# sd_flash_eeprom.net
KiCad netlist of a schematic drawn in Altium Designer
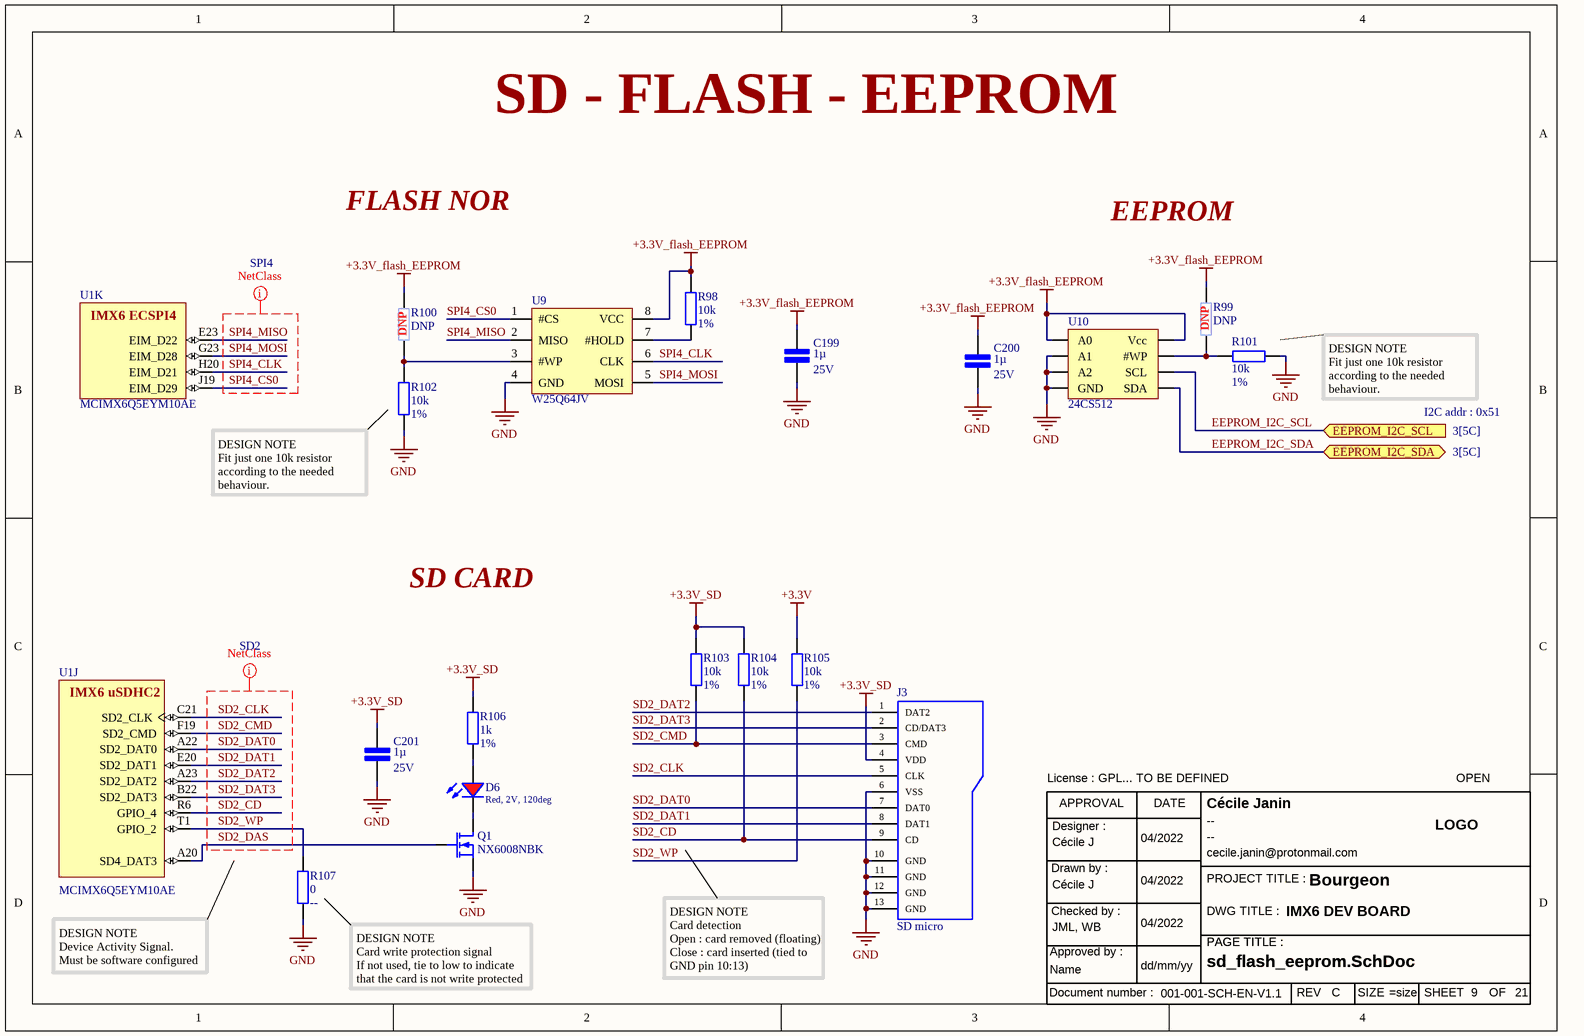
[diagram p0: sd_flash_eeprom.SchDoc]

(export (version "E")
  (design (tool "Eeschema 10.0.6"))
  (components
    (comp (ref "C199")
      (value "1µ")
      (footprint "Cap cer 0402/1005")
      (description "cap cer 1µ 25V 10% X5R 0402")
      (fields (field (name "TENSION DU DIÉLECTRIQUE") "25V"))
      (libsource (lib "First Board IMX6") (part "cap 1µ 25V"))
    )
    (comp (ref "C200")
      (value "1µ")
      (footprint "Cap cer 0402/1005")
      (description "cap cer 1µ 25V 10% X5R 0402")
      (fields (field (name "TENSION DU DIÉLECTRIQUE") "25V"))
      (libsource (lib "First Board IMX6") (part "cap 1µ 25V"))
    )
    (comp (ref "C201")
      (value "1µ")
      (footprint "Cap cer 0402/1005")
      (description "cap cer 1µ 25V 10% X5R 0402")
      (fields (field (name "TENSION DU DIÉLECTRIQUE") "25V"))
      (libsource (lib "First Board IMX6") (part "cap 1µ 25V"))
    )
    (comp (ref "D6")
      (value "Red, 2V, 120deg")
      (footprint "LED red 0603")
      (description "WL-SMCC SMD Mono-color Chip LED Compact, size 0603, Red, 2V, 120deg 150060RS73220")
      (fields (field (name "PART NUMBER") "150060RS73220") (field (name "PUBLISHER") "Wurth Elektronik"))
      (libsource (lib "First Board IMX6") (part "LED Red 0603"))
    )
    (comp (ref "J3")
      (value "SD micro")
      (footprint "SD_micro_693071020811")
      (description "SD micro card, push & push")
      (libsource (lib "First Board IMX6") (part "SD_micro_693071020811"))
    )
    (comp (ref "Q1")
      (value "NX6008NBK")
      (footprint "Sot-23-3 mosfet")
      (description "SOT-23-3 270mA 60V ESD protected 2kV HBM")
      (libsource (lib "First Board IMX6") (part "Tr nmos NX6008NBK"))
    )
    (comp (ref "R98")
      (value "10k")
      (footprint "Res 0402/1005")
      (description "res 10k 1% 0402")
      (fields (field (name "POURCENTAGE") "1%"))
      (libsource (lib "First Board IMX6") (part "res 10k 1%"))
    )
    (comp (ref "R99")
      (value "DNP")
      (footprint "Res 0402/1005")
      (description "res DNP 0403")
      (libsource (lib "First Board IMX6") (part "res DNP 0402"))
    )
    (comp (ref "R100")
      (value "DNP")
      (footprint "Res 0402/1005")
      (description "res DNP 0403")
      (libsource (lib "First Board IMX6") (part "res DNP 0402"))
    )
    (comp (ref "R101")
      (value "10k")
      (footprint "Res 0402/1005")
      (description "res 10k 1% 0402")
      (fields (field (name "POURCENTAGE") "1%"))
      (libsource (lib "First Board IMX6") (part "res 10k 1%"))
    )
    (comp (ref "R102")
      (value "10k")
      (footprint "Res 0402/1005")
      (description "res 10k 1% 0402")
      (fields (field (name "POURCENTAGE") "1%"))
      (libsource (lib "First Board IMX6") (part "res 10k 1%"))
    )
    (comp (ref "R103")
      (value "10k")
      (footprint "Res 0402/1005")
      (description "res 10k 1% 0402")
      (fields (field (name "POURCENTAGE") "1%"))
      (libsource (lib "First Board IMX6") (part "res 10k 1%"))
    )
    (comp (ref "R104")
      (value "10k")
      (footprint "Res 0402/1005")
      (description "res 10k 1% 0402")
      (fields (field (name "POURCENTAGE") "1%"))
      (libsource (lib "First Board IMX6") (part "res 10k 1%"))
    )
    (comp (ref "R105")
      (value "10k")
      (footprint "Res 0402/1005")
      (description "res 10k 1% 0402")
      (fields (field (name "POURCENTAGE") "1%"))
      (libsource (lib "First Board IMX6") (part "res 10k 1%"))
    )
    (comp (ref "R106")
      (value "1k")
      (footprint "Res 0402/1005")
      (description "res 1k 1% 0402")
      (fields (field (name "POURCENTAGE") "1%"))
      (libsource (lib "First Board IMX6") (part "res 1k 1%"))
    )
    (comp (ref "R107")
      (value "0")
      (footprint "Res 0603/1603")
      (description "res 0603")
      (fields (field (name "POURCENTAGE") "--"))
      (libsource (lib "First Board IMX6") (part "res 0Ohm"))
    )
    (comp (ref "TB8")
      (value "Title bloc ANSI modified")
      (libsource (lib "First Board IMX6") (part "Title bloc ANSI"))
    )
    (comp (ref "U1")
      (value "MCIMX6Q5EYM10AE")
      (footprint "FRES-2197-01")
      (fields
        (field (name "PARTNUMBER") "MCIMX6Q5EYM10ACR")
        (field (name "MANUFACTURER") "Freescale Semiconductor")
      )
      (libsource (lib "First Board IMX6") (part "IMX6Q5EYM10AE"))
    )
    (comp (ref "U9")
      (value "W25Q64JV")
      (footprint "SOIC 8 pin FLSH (longer)")
      (description "64Mbit flash NOR")
      (libsource (lib "First Board IMX6") (part "IC W25Q64JV"))
    )
    (comp (ref "U10")
      (value "24CS512")
      (footprint "soic-8")
      (description "EEPROM 512kbit")
      (libsource (lib "First Board IMX6") (part "IC 24CS512"))
    )
  )
  (nets
    (net (code "1") (name "+3.3V") (class "Default") (node (ref "R105") (pin "2") (pintype "passive")))
    (net (code "2") (name "+3.3V_SD") (class "Default")
      (node (ref "C201") (pin "1") (pinfunction "3_1") (pintype "passive"))
      (node (ref "J3") (pin "4") (pinfunction "VDD_4") (pintype "passive"))
      (node (ref "R103") (pin "2") (pintype "passive"))
      (node (ref "R104") (pin "2") (pintype "passive"))
      (node (ref "R106") (pin "2") (pintype "passive"))
    )
    (net (code "3") (name "+3.3V_flash_EEPROM") (class "Default")
      (node (ref "C199") (pin "1") (pinfunction "3_1") (pintype "passive"))
      (node (ref "C200") (pin "1") (pinfunction "3_1") (pintype "passive"))
      (node (ref "R100") (pin "2") (pintype "passive"))
      (node (ref "R98") (pin "2") (pintype "passive"))
      (node (ref "R99") (pin "2") (pintype "passive"))
      (node (ref "U10") (pin "1") (pinfunction "A0_1") (pintype "passive"))
      (node (ref "U10") (pin "8") (pinfunction "Vcc_8") (pintype "passive"))
      (node (ref "U9") (pin "8") (pinfunction "VCC_8") (pintype "passive"))
    )
    (net (code "4") (name "/EEPROM_I2C_SCL") (class "Default")
      (node (ref "U10") (pin "6") (pinfunction "SCL_6") (pintype "passive"))
    )
    (net (code "5") (name "/EEPROM_I2C_SDA") (class "Default")
      (node (ref "U10") (pin "5") (pinfunction "SDA_5") (pintype "passive"))
    )
    (net (code "6") (name "/SD2_CD") (class "Default")
      (node (ref "J3") (pin "9") (pinfunction "CD_9") (pintype "passive"))
      (node (ref "R104") (pin "1") (pintype "passive"))
      (node (ref "U1") (pin "R6") (pinfunction "GPIO_4_R6") (pintype "bidirectional"))
    )
    (net (code "7") (name "/SD2_CLK") (class "Default")
      (node (ref "J3") (pin "5") (pinfunction "CLK_5") (pintype "passive"))
      (node (ref "U1") (pin "C21") (pinfunction "SD2_CLK_C21") (pintype "bidirectional"))
    )
    (net (code "8") (name "/SD2_CMD") (class "Default")
      (node (ref "J3") (pin "3") (pinfunction "CMD_3") (pintype "passive"))
      (node (ref "R103") (pin "1") (pintype "passive"))
      (node (ref "U1") (pin "F19") (pinfunction "SD2_CMD_F19") (pintype "bidirectional"))
    )
    (net (code "9") (name "/SD2_DAS") (class "Default")
      (node (ref "Q1") (pin "G") (pinfunction "G_G") (pintype "passive"))
      (node (ref "U1") (pin "A20") (pinfunction "SD4_DAT3_A20") (pintype "bidirectional"))
    )
    (net (code "10") (name "/SD2_DAT0") (class "Default")
      (node (ref "J3") (pin "7") (pinfunction "DAT0_7") (pintype "passive"))
      (node (ref "U1") (pin "A22") (pinfunction "SD2_DAT0_A22") (pintype "bidirectional"))
    )
    (net (code "11") (name "/SD2_DAT1") (class "Default")
      (node (ref "J3") (pin "8") (pinfunction "DAT1_8") (pintype "passive"))
      (node (ref "U1") (pin "E20") (pinfunction "SD2_DAT1_E20") (pintype "bidirectional"))
    )
    (net (code "12") (name "/SD2_DAT2") (class "Default")
      (node (ref "J3") (pin "1") (pinfunction "DAT2_1") (pintype "passive"))
      (node (ref "U1") (pin "A23") (pinfunction "SD2_DAT2_A23") (pintype "bidirectional"))
    )
    (net (code "13") (name "/SD2_DAT3") (class "Default")
      (node (ref "J3") (pin "2") (pinfunction "CD/DAT3_2") (pintype "passive"))
      (node (ref "U1") (pin "B22") (pinfunction "SD2_DAT3_B22") (pintype "bidirectional"))
    )
    (net (code "14") (name "/SD2_WP") (class "Default")
      (node (ref "R105") (pin "1") (pintype "passive"))
      (node (ref "R107") (pin "2") (pintype "passive"))
      (node (ref "U1") (pin "T1") (pinfunction "GPIO_2_T1") (pintype "bidirectional"))
    )
    (net (code "15") (name "/SPI4_CLK") (class "Default")
      (node (ref "U1") (pin "H20") (pinfunction "EIM_D21_H20") (pintype "bidirectional"))
      (node (ref "U9") (pin "6") (pinfunction "CLK_6") (pintype "passive"))
    )
    (net (code "16") (name "/SPI4_CS0") (class "Default")
      (node (ref "U1") (pin "J19") (pinfunction "EIM_D29_J19") (pintype "bidirectional"))
      (node (ref "U9") (pin "1") (pinfunction "#CS_1") (pintype "passive"))
    )
    (net (code "17") (name "/SPI4_MISO") (class "Default")
      (node (ref "U1") (pin "E23") (pinfunction "EIM_D22_E23") (pintype "bidirectional"))
      (node (ref "U9") (pin "2") (pinfunction "MISO_2") (pintype "passive"))
    )
    (net (code "18") (name "/SPI4_MOSI") (class "Default")
      (node (ref "U1") (pin "G23") (pinfunction "EIM_D28_G23") (pintype "bidirectional"))
      (node (ref "U9") (pin "5") (pinfunction "MOSI_5") (pintype "passive"))
    )
    (net (code "19") (name "GND") (class "Default")
      (node (ref "C199") (pin "2") (pinfunction "4_2") (pintype "passive"))
      (node (ref "C200") (pin "2") (pinfunction "4_2") (pintype "passive"))
      (node (ref "C201") (pin "2") (pinfunction "4_2") (pintype "passive"))
      (node (ref "J3") (pin "10") (pinfunction "GND_10") (pintype "passive"))
      (node (ref "J3") (pin "11") (pinfunction "GND_11") (pintype "passive"))
      (node (ref "J3") (pin "12") (pinfunction "GND_12") (pintype "passive"))
      (node (ref "J3") (pin "13") (pinfunction "GND_13") (pintype "passive"))
      (node (ref "J3") (pin "6") (pinfunction "VSS_6") (pintype "passive"))
      (node (ref "Q1") (pin "S") (pinfunction "S_S") (pintype "passive"))
      (node (ref "R101") (pin "1") (pintype "passive"))
      (node (ref "R102") (pin "1") (pintype "passive"))
      (node (ref "R107") (pin "1") (pintype "passive"))
      (node (ref "U10") (pin "2") (pinfunction "A1_2") (pintype "passive"))
      (node (ref "U10") (pin "3") (pinfunction "A2_3") (pintype "passive"))
      (node (ref "U10") (pin "4") (pinfunction "GND_4") (pintype "passive"))
      (node (ref "U9") (pin "4") (pinfunction "GND_4") (pintype "passive"))
    )
    (net (code "20") (name "Net-(D6-A)") (class "Default")
      (node (ref "D6") (pin "2") (pinfunction "A_2") (pintype "passive"))
      (node (ref "R106") (pin "1") (pintype "passive"))
    )
    (net (code "21") (name "Net-(D6-K)") (class "Default")
      (node (ref "D6") (pin "1") (pinfunction "K_1") (pintype "passive"))
      (node (ref "Q1") (pin "D") (pinfunction "D_D") (pintype "passive"))
    )
    (net (code "22") (name "Net-(U9-#HOLD)") (class "Default")
      (node (ref "R98") (pin "1") (pintype "passive"))
      (node (ref "U9") (pin "7") (pinfunction "#HOLD_7") (pintype "passive"))
    )
    (net (code "23") (name "Net-(U9-#WP)") (class "Default")
      (node (ref "R100") (pin "1") (pintype "passive"))
      (node (ref "R102") (pin "2") (pintype "passive"))
      (node (ref "U9") (pin "3") (pinfunction "#WP_3") (pintype "passive"))
    )
    (net (code "24") (name "Net-(U10-#WP)") (class "Default")
      (node (ref "R101") (pin "2") (pintype "passive"))
      (node (ref "R99") (pin "1") (pintype "passive"))
      (node (ref "U10") (pin "7") (pinfunction "#WP_7") (pintype "passive"))
    )
  )
)
